# BNO055_module.net
KiCad netlist of a schematic drawn in Altium Designer
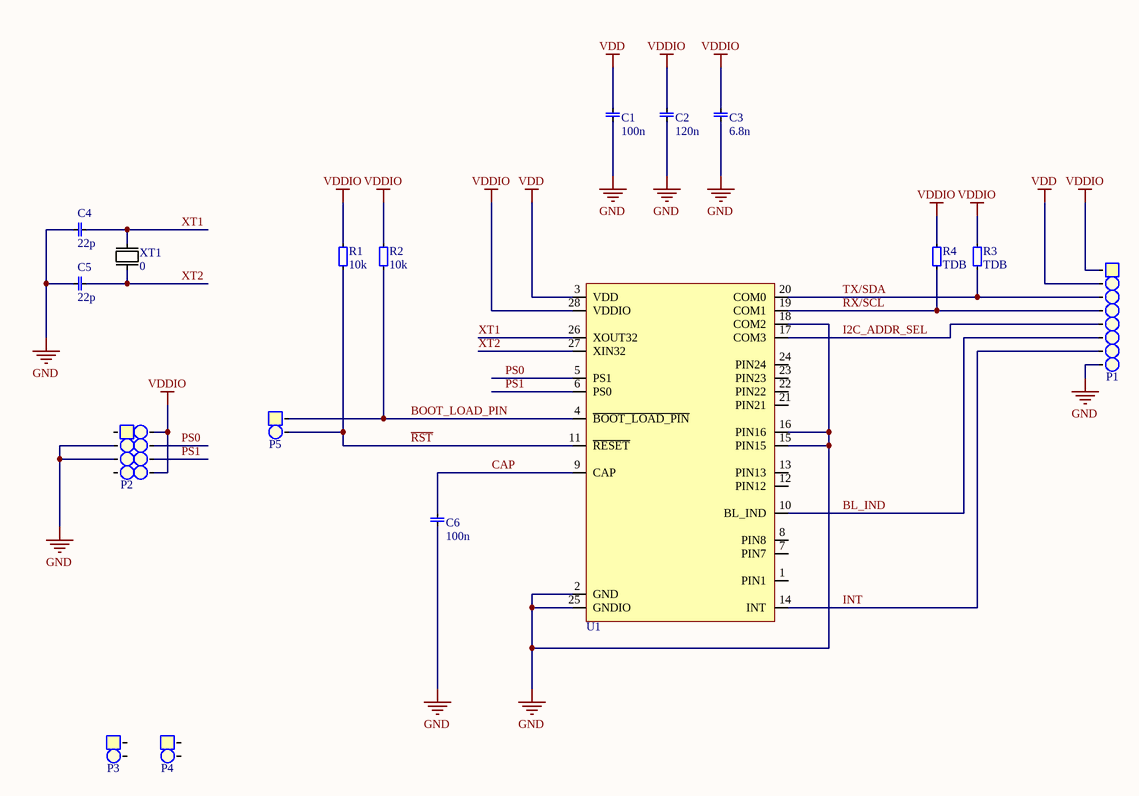
[diagram p0: BNO055_module.SchDoc]

(export (version "E")
  (design (tool "Eeschema 10.0.6"))
  (components
    (comp (ref "C1")
      (value "100n")
      (footprint "0603 cap")
      (fields (field (name "Comment") "0603, capacitor"))
      (libsource (lib "jclib") (part "0603, capacitor"))
    )
    (comp (ref "C2")
      (value "120n")
      (footprint "0603 cap")
      (fields (field (name "Comment") "0603, capacitor"))
      (libsource (lib "jclib") (part "0603, capacitor"))
    )
    (comp (ref "C3")
      (value "6.8n")
      (footprint "0603 cap")
      (fields (field (name "Comment") "0603, capacitor"))
      (libsource (lib "jclib") (part "0603, capacitor"))
    )
    (comp (ref "C4")
      (value "22p")
      (footprint "0603 cap")
      (fields (field (name "Comment") "0603, capacitor"))
      (libsource (lib "jclib") (part "0603, capacitor"))
    )
    (comp (ref "C5")
      (value "22p")
      (footprint "0603 cap")
      (fields (field (name "Comment") "0603, capacitor"))
      (libsource (lib "jclib") (part "0603, capacitor"))
    )
    (comp (ref "C6")
      (value "100n")
      (footprint "0603 cap")
      (fields (field (name "Comment") "0603, capacitor"))
      (libsource (lib "jclib") (part "0603, capacitor"))
    )
    (comp (ref "P1")
      (value "1x8 Pin Header")
      (footprint "1x8 Pin HEader")
      (description "2.54 mm")
      (libsource (lib "jclib") (part "1x8 Pin Header"))
    )
    (comp (ref "P2")
      (value "2x4 Pin Header")
      (footprint "2X4 PH")
      (description "2.54mm,")
      (libsource (lib "jclib") (part "2x4 Pin Header"))
    )
    (comp (ref "P3")
      (value "1x2 Pin Header")
      (footprint "padtwo_L")
      (description "2.54 mm, TH")
      (libsource (lib "jclib") (part "1x2 Pin Header"))
    )
    (comp (ref "P4")
      (value "1x2 Pin Header")
      (footprint "padtwo_L")
      (description "2.54 mm, TH")
      (libsource (lib "jclib") (part "1x2 Pin Header"))
    )
    (comp (ref "P5")
      (value "1x2 Pin Header")
      (footprint "padtwo_L")
      (description "2.54 mm, TH")
      (libsource (lib "jclib") (part "1x2 Pin Header"))
    )
    (comp (ref "R1")
      (value "10k")
      (footprint "0603")
      (fields (field (name "Comment") "0603, resistor"))
      (libsource (lib "jclib") (part "0603, resistor"))
    )
    (comp (ref "R2")
      (value "10k")
      (footprint "0603")
      (fields (field (name "Comment") "0603, resistor"))
      (libsource (lib "jclib") (part "0603, resistor"))
    )
    (comp (ref "R3")
      (value "TDB")
      (footprint "0603")
      (fields (field (name "Comment") "0603, resistor"))
      (libsource (lib "jclib") (part "0603, resistor"))
    )
    (comp (ref "R4")
      (value "TDB")
      (footprint "0603")
      (fields (field (name "Comment") "0603, resistor"))
      (libsource (lib "jclib") (part "0603, resistor"))
    )
    (comp (ref "U1")
      (value "BNO055")
      (footprint "BNO055")
      (description "Accelerometer, gyroskop, magnetometer, 9 axis Sensor I²C, UART Output")
      (libsource (lib "jclib") (part "BNO055"))
    )
    (comp (ref "XT1")
      (value "0")
      (footprint "XTAL_SMD_LP")
      (description "16 MHz, SMD, 5mm x 3,2mm, 30 ppm")
      (fields (field (name "Comment") "XTAL TXC 7A"))
      (libsource (lib "jclib") (part "XTAL TXC 7A"))
    )
  )
  (nets
    (net (code "1") (name "/BL_IND") (class "Default")
      (node (ref "P1") (pin "6") (pinfunction "6_6") (pintype "passive"))
      (node (ref "U1") (pin "10") (pinfunction "BL_IND_10") (pintype "passive"))
    )
    (net (code "2") (name "/BOOT_LOAD_PIN") (class "Default")
      (node (ref "P5") (pin "1") (pinfunction "1_1") (pintype "passive"))
      (node (ref "R2") (pin "1") (pinfunction "1_1") (pintype "passive"))
      (node (ref "U1") (pin "4") (pinfunction "~{BOOT_LOAD_PIN}_4") (pintype "passive"))
    )
    (net (code "3") (name "/CAP") (class "Default")
      (node (ref "C6") (pin "1") (pinfunction "1_1") (pintype "passive"))
      (node (ref "U1") (pin "9") (pinfunction "CAP_9") (pintype "passive"))
    )
    (net (code "4") (name "/I2C_ADDR_SEL") (class "Default")
      (node (ref "P1") (pin "5") (pinfunction "5_5") (pintype "passive"))
      (node (ref "U1") (pin "17") (pinfunction "COM3_17") (pintype "passive"))
    )
    (net (code "5") (name "/INT") (class "Default")
      (node (ref "P1") (pin "7") (pinfunction "7_7") (pintype "passive"))
      (node (ref "U1") (pin "14") (pinfunction "INT_14") (pintype "passive"))
    )
    (net (code "6") (name "/PS0") (class "Default")
      (node (ref "P2") (pin "7") (pinfunction "7_7") (pintype "passive"))
      (node (ref "U1") (pin "5") (pinfunction "PS1_5") (pintype "passive"))
    )
    (net (code "7") (name "/PS1") (class "Default")
      (node (ref "P2") (pin "6") (pinfunction "6_6") (pintype "passive"))
      (node (ref "U1") (pin "6") (pinfunction "PS0_6") (pintype "passive"))
    )
    (net (code "8") (name "/RX{slash}SCL") (class "Default")
      (node (ref "P1") (pin "4") (pinfunction "4_4") (pintype "passive"))
      (node (ref "R4") (pin "1") (pinfunction "1_1") (pintype "passive"))
      (node (ref "U1") (pin "19") (pinfunction "COM1_19") (pintype "passive"))
    )
    (net (code "9") (name "/TX{slash}SDA") (class "Default")
      (node (ref "P1") (pin "3") (pinfunction "3_3") (pintype "passive"))
      (node (ref "R3") (pin "1") (pinfunction "1_1") (pintype "passive"))
      (node (ref "U1") (pin "20") (pinfunction "COM0_20") (pintype "passive"))
    )
    (net (code "10") (name "/XT1") (class "Default")
      (node (ref "C4") (pin "1") (pinfunction "1_1") (pintype "passive"))
      (node (ref "U1") (pin "26") (pinfunction "XOUT32_26") (pintype "passive"))
      (node (ref "XT1") (pin "2") (pinfunction "2_2") (pintype "passive"))
    )
    (net (code "11") (name "/XT2") (class "Default")
      (node (ref "C5") (pin "1") (pinfunction "1_1") (pintype "passive"))
      (node (ref "U1") (pin "27") (pinfunction "XIN32_27") (pintype "passive"))
      (node (ref "XT1") (pin "1") (pinfunction "1_1") (pintype "passive"))
    )
    (net (code "12") (name "/~{RST}") (class "Default")
      (node (ref "P5") (pin "2") (pinfunction "2_2") (pintype "passive"))
      (node (ref "R1") (pin "1") (pinfunction "1_1") (pintype "passive"))
      (node (ref "U1") (pin "11") (pinfunction "~{RESET}_11") (pintype "passive"))
    )
    (net (code "13") (name "GND") (class "Default")
      (node (ref "C1") (pin "0") (pinfunction "0_0") (pintype "passive"))
      (node (ref "C2") (pin "0") (pinfunction "0_0") (pintype "passive"))
      (node (ref "C3") (pin "0") (pinfunction "0_0") (pintype "passive"))
      (node (ref "C4") (pin "0") (pinfunction "0_0") (pintype "passive"))
      (node (ref "C5") (pin "0") (pinfunction "0_0") (pintype "passive"))
      (node (ref "C6") (pin "0") (pinfunction "0_0") (pintype "passive"))
      (node (ref "P1") (pin "8") (pinfunction "8_8") (pintype "passive"))
      (node (ref "P2") (pin "2") (pinfunction "2_2") (pintype "passive"))
      (node (ref "P2") (pin "3") (pinfunction "3_3") (pintype "passive"))
      (node (ref "U1") (pin "15") (pinfunction "PIN15_15") (pintype "passive"))
      (node (ref "U1") (pin "16") (pinfunction "PIN16_16") (pintype "passive"))
      (node (ref "U1") (pin "18") (pinfunction "COM2_18") (pintype "passive"))
      (node (ref "U1") (pin "2") (pinfunction "GND_2") (pintype "passive"))
      (node (ref "U1") (pin "25") (pinfunction "GNDIO_25") (pintype "passive"))
    )
    (net (code "14") (name "VDD") (class "Default")
      (node (ref "C1") (pin "1") (pinfunction "1_1") (pintype "passive"))
      (node (ref "P1") (pin "2") (pinfunction "2_2") (pintype "passive"))
      (node (ref "U1") (pin "3") (pinfunction "VDD_3") (pintype "passive"))
    )
    (net (code "15") (name "VDDIO") (class "Default")
      (node (ref "C2") (pin "1") (pinfunction "1_1") (pintype "passive"))
      (node (ref "C3") (pin "1") (pinfunction "1_1") (pintype "passive"))
      (node (ref "P1") (pin "1") (pinfunction "1_1") (pintype "passive"))
      (node (ref "P2") (pin "5") (pinfunction "5_5") (pintype "passive"))
      (node (ref "P2") (pin "8") (pinfunction "8_8") (pintype "passive"))
      (node (ref "R1") (pin "0") (pinfunction "0_0") (pintype "passive"))
      (node (ref "R2") (pin "0") (pinfunction "0_0") (pintype "passive"))
      (node (ref "R3") (pin "0") (pinfunction "0_0") (pintype "passive"))
      (node (ref "R4") (pin "0") (pinfunction "0_0") (pintype "passive"))
      (node (ref "U1") (pin "28") (pinfunction "VDDIO_28") (pintype "passive"))
    )
    (net (code "16") (name "unconnected-(P2-Pad1)") (class "Default")
      (node (ref "P2") (pin "1") (pinfunction "1_1") (pintype "passive"))
    )
    (net (code "17") (name "unconnected-(P2-Pad4)") (class "Default")
      (node (ref "P2") (pin "4") (pinfunction "4_4") (pintype "passive"))
    )
    (net (code "18") (name "unconnected-(P3-Pad1)") (class "Default")
      (node (ref "P3") (pin "1") (pinfunction "1_1") (pintype "passive"))
    )
    (net (code "19") (name "unconnected-(P3-Pad2)") (class "Default")
      (node (ref "P3") (pin "2") (pinfunction "2_2") (pintype "passive"))
    )
    (net (code "20") (name "unconnected-(P4-Pad1)") (class "Default")
      (node (ref "P4") (pin "1") (pinfunction "1_1") (pintype "passive"))
    )
    (net (code "21") (name "unconnected-(P4-Pad2)") (class "Default")
      (node (ref "P4") (pin "2") (pinfunction "2_2") (pintype "passive"))
    )
    (net (code "22") (name "unconnected-(U1-PIN1-Pad1)") (class "Default")
      (node (ref "U1") (pin "1") (pinfunction "PIN1_1") (pintype "passive"))
    )
    (net (code "23") (name "unconnected-(U1-PIN7-Pad7)") (class "Default")
      (node (ref "U1") (pin "7") (pinfunction "PIN7_7") (pintype "passive"))
    )
    (net (code "24") (name "unconnected-(U1-PIN8-Pad8)") (class "Default")
      (node (ref "U1") (pin "8") (pinfunction "PIN8_8") (pintype "passive"))
    )
    (net (code "25") (name "unconnected-(U1-PIN12-Pad12)") (class "Default")
      (node (ref "U1") (pin "12") (pinfunction "PIN12_12") (pintype "passive"))
    )
    (net (code "26") (name "unconnected-(U1-PIN13-Pad13)") (class "Default")
      (node (ref "U1") (pin "13") (pinfunction "PIN13_13") (pintype "passive"))
    )
    (net (code "27") (name "unconnected-(U1-PIN21-Pad21)") (class "Default")
      (node (ref "U1") (pin "21") (pinfunction "PIN21_21") (pintype "passive"))
    )
    (net (code "28") (name "unconnected-(U1-PIN22-Pad22)") (class "Default")
      (node (ref "U1") (pin "22") (pinfunction "PIN22_22") (pintype "passive"))
    )
    (net (code "29") (name "unconnected-(U1-PIN23-Pad23)") (class "Default")
      (node (ref "U1") (pin "23") (pinfunction "PIN23_23") (pintype "passive"))
    )
    (net (code "30") (name "unconnected-(U1-PIN24-Pad24)") (class "Default")
      (node (ref "U1") (pin "24") (pinfunction "PIN24_24") (pintype "passive"))
    )
  )
)
